# motors-overview.net
KiCad netlist of a schematic drawn in Altium Designer
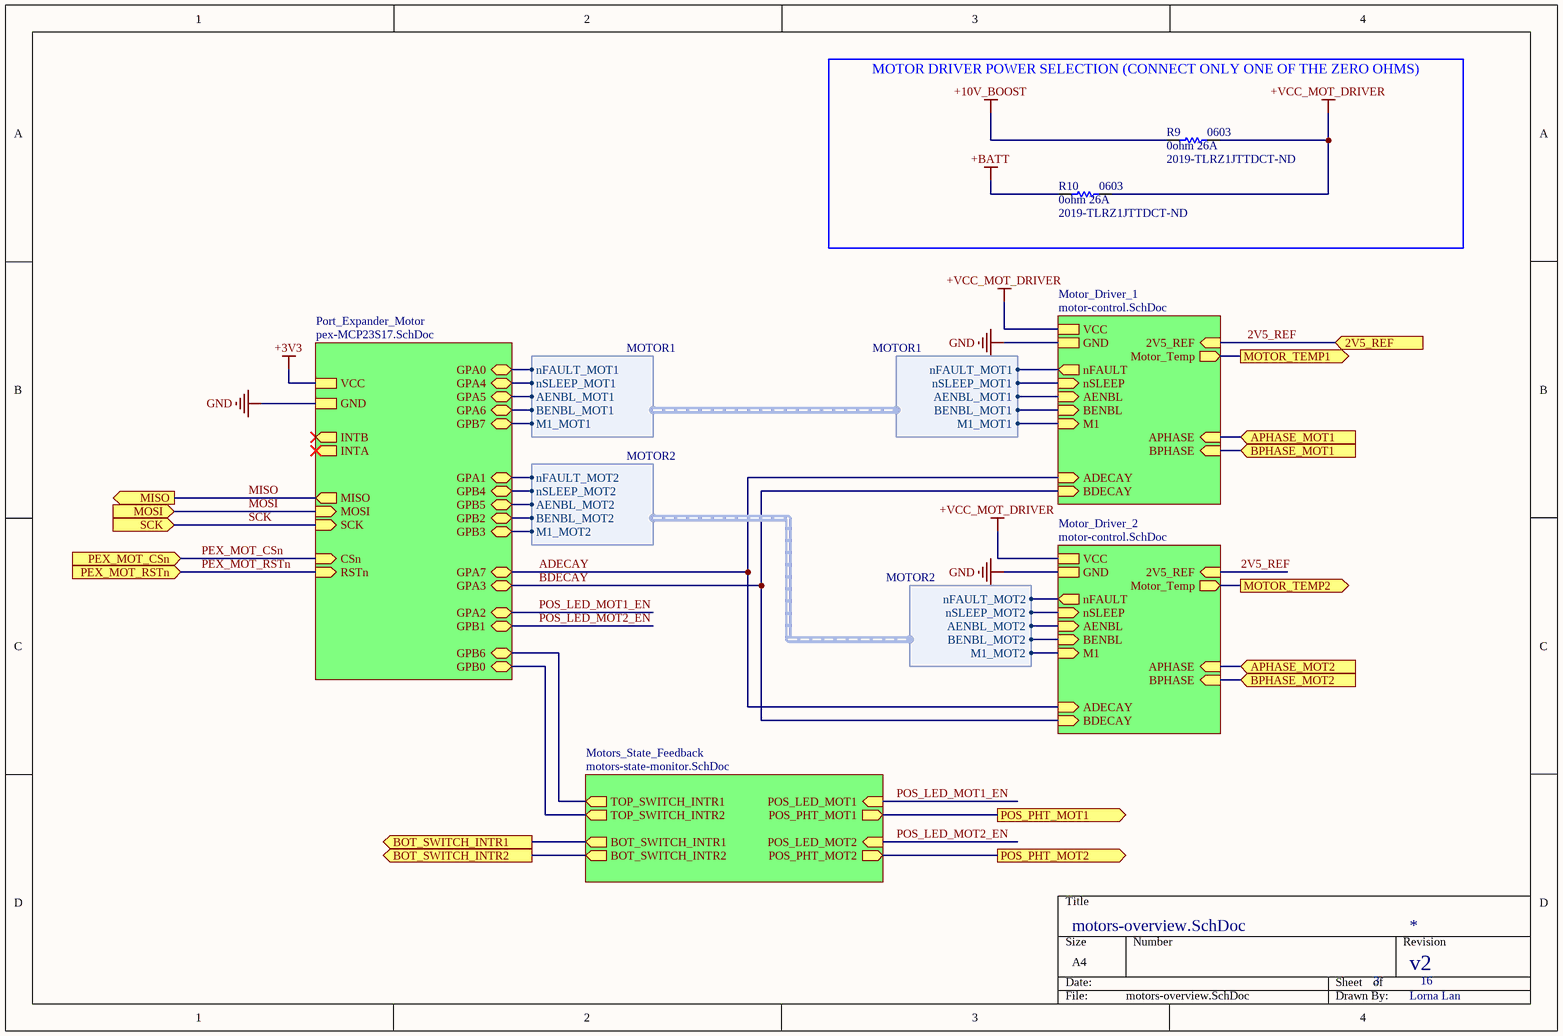
[diagram p0: motors-overview.SchDoc]

(export (version "E")
  (design (tool "Eeschema 10.0.6"))
  (components
    (comp (ref "R9")
      (value "0603")
      (footprint "RES0603R")
      (description "0603 resistor")
      (fields
        (field (name "ALTIUM_VALUE") "0ohm 26A")
        (field (name "SUPPLIER PART NUMBER 1") "2019-TLRZ1JTTDCT-ND")
      )
      (libsource (lib "RES0603") (part "RES0603"))
    )
    (comp (ref "R10")
      (value "0603")
      (footprint "RES0603R")
      (description "0603 resistor")
      (fields
        (field (name "ALTIUM_VALUE") "0ohm 26A")
        (field (name "SUPPLIER PART NUMBER 1") "2019-TLRZ1JTTDCT-ND")
      )
      (libsource (lib "RES0603") (part "RES0603"))
    )
  )
  (nets
    (net (code "4") (name "+10V_BOOST") (class "Default")
      (node (ref "R9") (pin "1") (pinfunction "1_1") (pintype "passive"))
    )
    (net (code "5") (name "+BATT") (class "Default")
      (node (ref "R10") (pin "1") (pinfunction "1_1") (pintype "passive"))
    )
    (net (code "6") (name "+VCC_MOT_DRIVER") (class "Default")
      (node (ref "R10") (pin "2") (pinfunction "2_2") (pintype "passive"))
      (node (ref "R9") (pin "2") (pinfunction "2_2") (pintype "passive"))
    )
  )
)
